# M-Brain.net
KiCad netlist of a schematic drawn in EAGLE
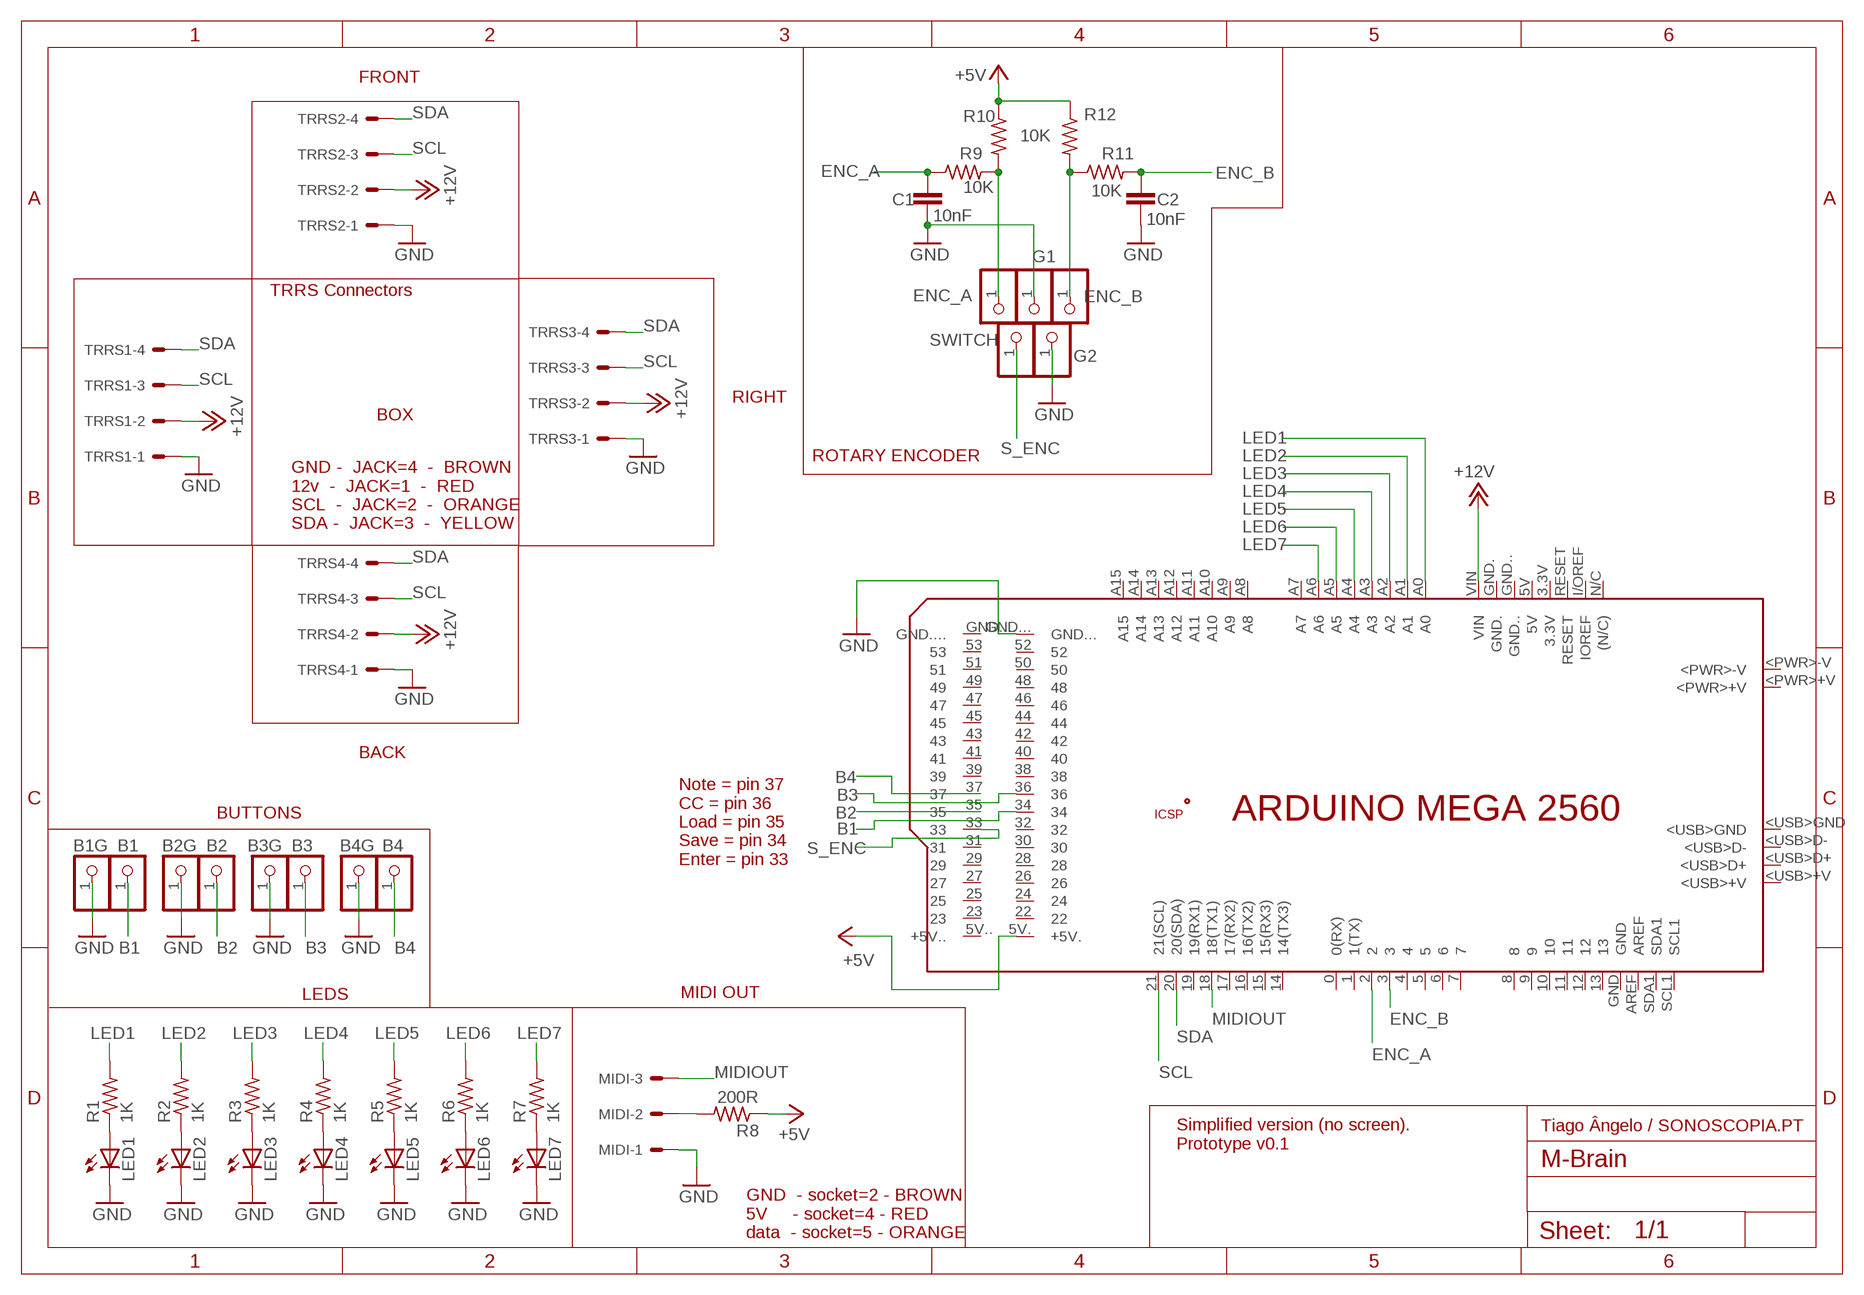
[diagram p0: schematic, sheet 1]

(export (version "E")
  (design (tool "Eeschema 10.0.6"))
  (components
    (comp (ref "B1")
      (value "PINHD-1X1")
      (footprint "eagle-import:1X01")
      (libsource (lib "eagle-import") (part "PINHD-1X1"))
    )
    (comp (ref "B1G")
      (value "PINHD-1X1")
      (footprint "eagle-import:1X01")
      (libsource (lib "eagle-import") (part "PINHD-1X1"))
    )
    (comp (ref "B2")
      (value "PINHD-1X1")
      (footprint "eagle-import:1X01")
      (libsource (lib "eagle-import") (part "PINHD-1X1"))
    )
    (comp (ref "B2G")
      (value "PINHD-1X1")
      (footprint "eagle-import:1X01")
      (libsource (lib "eagle-import") (part "PINHD-1X1"))
    )
    (comp (ref "B3")
      (value "PINHD-1X1")
      (footprint "eagle-import:1X01")
      (libsource (lib "eagle-import") (part "PINHD-1X1"))
    )
    (comp (ref "B3G")
      (value "PINHD-1X1")
      (footprint "eagle-import:1X01")
      (libsource (lib "eagle-import") (part "PINHD-1X1"))
    )
    (comp (ref "B4")
      (value "PINHD-1X1")
      (footprint "eagle-import:1X01")
      (libsource (lib "eagle-import") (part "PINHD-1X1"))
    )
    (comp (ref "B4G")
      (value "PINHD-1X1")
      (footprint "eagle-import:1X01")
      (libsource (lib "eagle-import") (part "PINHD-1X1"))
    )
    (comp (ref "C1")
      (value "10nF")
      (footprint "eagle-import:C2.5-2")
      (libsource (lib "eagle-import") (part "C2.5/2"))
    )
    (comp (ref "C2")
      (value "10nF")
      (footprint "eagle-import:C2.5-2")
      (libsource (lib "eagle-import") (part "C2.5/2"))
    )
    (comp (ref "ENC_A")
      (value "PINHD-1X1")
      (footprint "eagle-import:1X01")
      (libsource (lib "eagle-import") (part "PINHD-1X1"))
    )
    (comp (ref "ENC_B")
      (value "PINHD-1X1")
      (footprint "eagle-import:1X01")
      (libsource (lib "eagle-import") (part "PINHD-1X1"))
    )
    (comp (ref "G1")
      (value "PINHD-1X1")
      (footprint "eagle-import:1X01")
      (libsource (lib "eagle-import") (part "PINHD-1X1"))
    )
    (comp (ref "G2")
      (value "PINHD-1X1")
      (footprint "eagle-import:1X01")
      (libsource (lib "eagle-import") (part "PINHD-1X1"))
    )
    (comp (ref "LED1")
      (value "LED5MM")
      (footprint "eagle-import:LED5MM")
      (libsource (lib "eagle-import") (part "LED5MM"))
    )
    (comp (ref "LED2")
      (value "LED5MM")
      (footprint "eagle-import:LED5MM")
      (libsource (lib "eagle-import") (part "LED5MM"))
    )
    (comp (ref "LED3")
      (value "LED5MM")
      (footprint "eagle-import:LED5MM")
      (libsource (lib "eagle-import") (part "LED5MM"))
    )
    (comp (ref "LED4")
      (value "LED5MM")
      (footprint "eagle-import:LED5MM")
      (libsource (lib "eagle-import") (part "LED5MM"))
    )
    (comp (ref "LED5")
      (value "LED5MM")
      (footprint "eagle-import:LED5MM")
      (libsource (lib "eagle-import") (part "LED5MM"))
    )
    (comp (ref "LED6")
      (value "LED5MM")
      (footprint "eagle-import:LED5MM")
      (libsource (lib "eagle-import") (part "LED5MM"))
    )
    (comp (ref "LED7")
      (value "LED5MM")
      (footprint "eagle-import:LED5MM")
      (libsource (lib "eagle-import") (part "LED5MM"))
    )
    (comp (ref "MIDI")
      (value "22-27-2031-03")
      (footprint "eagle-import:6410-03")
      (libsource (lib "eagle-import") (part "22-?-0327-2031"))
    )
    (comp (ref "PCB1")
      (value "ARDUINO_MEGA2560")
      (footprint "eagle-import:ARDUINO_MEGA2560")
      (libsource (lib "eagle-import") (part "ARDUINO_MEGA2560"))
    )
    (comp (ref "R1")
      (value "1K")
      (footprint "eagle-import:0204_5")
      (libsource (lib "eagle-import") (part "R-US_0204/5"))
    )
    (comp (ref "R2")
      (value "1K")
      (footprint "eagle-import:0204_5")
      (libsource (lib "eagle-import") (part "R-US_0204/5"))
    )
    (comp (ref "R3")
      (value "1K")
      (footprint "eagle-import:0204_5")
      (libsource (lib "eagle-import") (part "R-US_0204/5"))
    )
    (comp (ref "R4")
      (value "1K")
      (footprint "eagle-import:0204_5")
      (libsource (lib "eagle-import") (part "R-US_0204/5"))
    )
    (comp (ref "R5")
      (value "1K")
      (footprint "eagle-import:0204_5")
      (libsource (lib "eagle-import") (part "R-US_0204/5"))
    )
    (comp (ref "R6")
      (value "1K")
      (footprint "eagle-import:0204_5")
      (libsource (lib "eagle-import") (part "R-US_0204/5"))
    )
    (comp (ref "R7")
      (value "1K")
      (footprint "eagle-import:0204_5")
      (libsource (lib "eagle-import") (part "R-US_0204/5"))
    )
    (comp (ref "R8")
      (value "200R")
      (footprint "eagle-import:0204_7")
      (libsource (lib "eagle-import") (part "R-US_0204/7"))
    )
    (comp (ref "R9")
      (value "10K")
      (footprint "eagle-import:0204_7")
      (libsource (lib "eagle-import") (part "R-US_0204/7"))
    )
    (comp (ref "R10")
      (value "10K")
      (footprint "eagle-import:0204_7")
      (libsource (lib "eagle-import") (part "R-US_0204/7"))
    )
    (comp (ref "R11")
      (value "10K")
      (footprint "eagle-import:0204_7")
      (libsource (lib "eagle-import") (part "R-US_0204/7"))
    )
    (comp (ref "R12")
      (value "10K")
      (footprint "eagle-import:0204_7")
      (libsource (lib "eagle-import") (part "R-US_0204/7"))
    )
    (comp (ref "SWITCH")
      (value "PINHD-1X1")
      (footprint "eagle-import:1X01")
      (libsource (lib "eagle-import") (part "PINHD-1X1"))
    )
    (comp (ref "TRRS1")
      (value "22-27-2041-04")
      (footprint "eagle-import:6410-04")
      (libsource (lib "eagle-import") (part "22-?-0427-2041"))
    )
    (comp (ref "TRRS2")
      (value "22-27-2041-04")
      (footprint "eagle-import:6410-04")
      (libsource (lib "eagle-import") (part "22-?-0427-2041"))
    )
    (comp (ref "TRRS3")
      (value "22-27-2041-04")
      (footprint "eagle-import:6410-04")
      (libsource (lib "eagle-import") (part "22-?-0427-2041"))
    )
    (comp (ref "TRRS4")
      (value "22-27-2041-04")
      (footprint "eagle-import:6410-04")
      (libsource (lib "eagle-import") (part "22-?-0427-2041"))
    )
  )
  (nets
    (net (code "1") (name "+5V") (class "Default")
      (node (ref "PCB1") (pin "5V.") (pinfunction "+5V._5V.") (pintype "bidirectional"))
      (node (ref "R10") (pin "1") (pinfunction "1_1") (pintype "passive"))
      (node (ref "R12") (pin "1") (pinfunction "1_1") (pintype "passive"))
      (node (ref "R8") (pin "1") (pinfunction "1_1") (pintype "passive"))
    )
    (net (code "2") (name "+12V") (class "Default")
      (node (ref "PCB1") (pin "VIN") (pinfunction "VIN_VIN") (pintype "bidirectional"))
      (node (ref "TRRS1") (pin "2") (pinfunction "S_2") (pintype "passive"))
      (node (ref "TRRS2") (pin "2") (pinfunction "S_2") (pintype "passive"))
      (node (ref "TRRS3") (pin "2") (pinfunction "S_2") (pintype "passive"))
      (node (ref "TRRS4") (pin "2") (pinfunction "S_2") (pintype "passive"))
    )
    (net (code "3") (name "/B1") (class "Default")
      (node (ref "B1") (pin "1") (pinfunction "1_1") (pintype "passive"))
      (node (ref "PCB1") (pin "34") (pinfunction "34_34") (pintype "bidirectional"))
    )
    (net (code "4") (name "/B2") (class "Default")
      (node (ref "B2") (pin "1") (pinfunction "1_1") (pintype "passive"))
      (node (ref "PCB1") (pin "35") (pinfunction "35_35") (pintype "bidirectional"))
    )
    (net (code "5") (name "/B3") (class "Default")
      (node (ref "B3") (pin "1") (pinfunction "1_1") (pintype "passive"))
      (node (ref "PCB1") (pin "36") (pinfunction "36_36") (pintype "bidirectional"))
    )
    (net (code "6") (name "/B4") (class "Default")
      (node (ref "B4") (pin "1") (pinfunction "1_1") (pintype "passive"))
      (node (ref "PCB1") (pin "37") (pinfunction "37_37") (pintype "bidirectional"))
    )
    (net (code "7") (name "/ENC_A") (class "Default")
      (node (ref "C1") (pin "1") (pinfunction "1_1") (pintype "passive"))
      (node (ref "PCB1") (pin "2") (pinfunction "2_2") (pintype "bidirectional"))
      (node (ref "R9") (pin "1") (pinfunction "1_1") (pintype "passive"))
    )
    (net (code "8") (name "/ENC_B") (class "Default")
      (node (ref "C2") (pin "1") (pinfunction "1_1") (pintype "passive"))
      (node (ref "PCB1") (pin "3") (pinfunction "3_3") (pintype "bidirectional"))
      (node (ref "R11") (pin "2") (pinfunction "2_2") (pintype "passive"))
    )
    (net (code "9") (name "/LED1") (class "Default")
      (node (ref "PCB1") (pin "A0") (pinfunction "A0_A0") (pintype "bidirectional"))
      (node (ref "R1") (pin "2") (pinfunction "2_2") (pintype "passive"))
    )
    (net (code "10") (name "/LED2") (class "Default")
      (node (ref "PCB1") (pin "A1") (pinfunction "A1_A1") (pintype "bidirectional"))
      (node (ref "R2") (pin "2") (pinfunction "2_2") (pintype "passive"))
    )
    (net (code "11") (name "/LED3") (class "Default")
      (node (ref "PCB1") (pin "A2") (pinfunction "A2_A2") (pintype "bidirectional"))
      (node (ref "R3") (pin "2") (pinfunction "2_2") (pintype "passive"))
    )
    (net (code "12") (name "/LED4") (class "Default")
      (node (ref "PCB1") (pin "A3") (pinfunction "A3_A3") (pintype "bidirectional"))
      (node (ref "R4") (pin "2") (pinfunction "2_2") (pintype "passive"))
    )
    (net (code "13") (name "/LED5") (class "Default")
      (node (ref "PCB1") (pin "A4") (pinfunction "A4_A4") (pintype "bidirectional"))
      (node (ref "R5") (pin "2") (pinfunction "2_2") (pintype "passive"))
    )
    (net (code "14") (name "/LED6") (class "Default")
      (node (ref "PCB1") (pin "A5") (pinfunction "A5_A5") (pintype "bidirectional"))
      (node (ref "R6") (pin "2") (pinfunction "2_2") (pintype "passive"))
    )
    (net (code "15") (name "/LED7") (class "Default")
      (node (ref "PCB1") (pin "A6") (pinfunction "A6_A6") (pintype "bidirectional"))
      (node (ref "R7") (pin "2") (pinfunction "2_2") (pintype "passive"))
    )
    (net (code "16") (name "/MIDIOUT") (class "Default")
      (node (ref "MIDI") (pin "3") (pinfunction "S_3") (pintype "passive"))
      (node (ref "PCB1") (pin "18") (pinfunction "18(TX1)_18") (pintype "bidirectional"))
    )
    (net (code "17") (name "/SCL") (class "Default")
      (node (ref "PCB1") (pin "21") (pinfunction "21(SCL)_21") (pintype "bidirectional"))
      (node (ref "TRRS1") (pin "3") (pinfunction "S_3") (pintype "passive"))
      (node (ref "TRRS2") (pin "3") (pinfunction "S_3") (pintype "passive"))
      (node (ref "TRRS3") (pin "3") (pinfunction "S_3") (pintype "passive"))
      (node (ref "TRRS4") (pin "3") (pinfunction "S_3") (pintype "passive"))
    )
    (net (code "18") (name "/SDA") (class "Default")
      (node (ref "PCB1") (pin "20") (pinfunction "20(SDA)_20") (pintype "bidirectional"))
      (node (ref "TRRS1") (pin "4") (pinfunction "S_4") (pintype "passive"))
      (node (ref "TRRS2") (pin "4") (pinfunction "S_4") (pintype "passive"))
      (node (ref "TRRS3") (pin "4") (pinfunction "S_4") (pintype "passive"))
      (node (ref "TRRS4") (pin "4") (pinfunction "S_4") (pintype "passive"))
    )
    (net (code "19") (name "/S_ENC") (class "Default")
      (node (ref "PCB1") (pin "33") (pinfunction "33_33") (pintype "bidirectional"))
      (node (ref "SWITCH") (pin "1") (pinfunction "1_1") (pintype "passive"))
    )
    (net (code "20") (name "GND") (class "Default")
      (node (ref "B1G") (pin "1") (pinfunction "1_1") (pintype "passive"))
      (node (ref "B2G") (pin "1") (pinfunction "1_1") (pintype "passive"))
      (node (ref "B3G") (pin "1") (pinfunction "1_1") (pintype "passive"))
      (node (ref "B4G") (pin "1") (pinfunction "1_1") (pintype "passive"))
      (node (ref "C1") (pin "2") (pinfunction "2_2") (pintype "passive"))
      (node (ref "C2") (pin "2") (pinfunction "2_2") (pintype "passive"))
      (node (ref "G1") (pin "1") (pinfunction "1_1") (pintype "passive"))
      (node (ref "G2") (pin "1") (pinfunction "1_1") (pintype "passive"))
      (node (ref "LED1") (pin "K") (pinfunction "C_K") (pintype "passive"))
      (node (ref "LED2") (pin "K") (pinfunction "C_K") (pintype "passive"))
      (node (ref "LED3") (pin "K") (pinfunction "C_K") (pintype "passive"))
      (node (ref "LED4") (pin "K") (pinfunction "C_K") (pintype "passive"))
      (node (ref "LED5") (pin "K") (pinfunction "C_K") (pintype "passive"))
      (node (ref "LED6") (pin "K") (pinfunction "C_K") (pintype "passive"))
      (node (ref "LED7") (pin "K") (pinfunction "C_K") (pintype "passive"))
      (node (ref "MIDI") (pin "1") (pinfunction "S_1") (pintype "passive"))
      (node (ref "PCB1") (pin "GND...") (pinfunction "GND..._GND...") (pintype "bidirectional"))
      (node (ref "TRRS1") (pin "1") (pinfunction "S_1") (pintype "passive"))
      (node (ref "TRRS2") (pin "1") (pinfunction "S_1") (pintype "passive"))
      (node (ref "TRRS3") (pin "1") (pinfunction "S_1") (pintype "passive"))
      (node (ref "TRRS4") (pin "1") (pinfunction "S_1") (pintype "passive"))
    )
    (net (code "21") (name "Net-(ENC_A-Pad1)") (class "Default")
      (node (ref "ENC_A") (pin "1") (pinfunction "1_1") (pintype "passive"))
      (node (ref "R10") (pin "2") (pinfunction "2_2") (pintype "passive"))
      (node (ref "R9") (pin "2") (pinfunction "2_2") (pintype "passive"))
    )
    (net (code "22") (name "Net-(ENC_B-Pad1)") (class "Default")
      (node (ref "ENC_B") (pin "1") (pinfunction "1_1") (pintype "passive"))
      (node (ref "R11") (pin "1") (pinfunction "1_1") (pintype "passive"))
      (node (ref "R12") (pin "2") (pinfunction "2_2") (pintype "passive"))
    )
    (net (code "23") (name "Net-(LED1-PadA)") (class "Default")
      (node (ref "LED1") (pin "A") (pinfunction "A_A") (pintype "passive"))
      (node (ref "R1") (pin "1") (pinfunction "1_1") (pintype "passive"))
    )
    (net (code "24") (name "Net-(LED2-PadA)") (class "Default")
      (node (ref "LED2") (pin "A") (pinfunction "A_A") (pintype "passive"))
      (node (ref "R2") (pin "1") (pinfunction "1_1") (pintype "passive"))
    )
    (net (code "25") (name "Net-(LED3-PadA)") (class "Default")
      (node (ref "LED3") (pin "A") (pinfunction "A_A") (pintype "passive"))
      (node (ref "R3") (pin "1") (pinfunction "1_1") (pintype "passive"))
    )
    (net (code "26") (name "Net-(LED4-PadA)") (class "Default")
      (node (ref "LED4") (pin "A") (pinfunction "A_A") (pintype "passive"))
      (node (ref "R4") (pin "1") (pinfunction "1_1") (pintype "passive"))
    )
    (net (code "27") (name "Net-(LED5-PadA)") (class "Default")
      (node (ref "LED5") (pin "A") (pinfunction "A_A") (pintype "passive"))
      (node (ref "R5") (pin "1") (pinfunction "1_1") (pintype "passive"))
    )
    (net (code "28") (name "Net-(LED6-PadA)") (class "Default")
      (node (ref "LED6") (pin "A") (pinfunction "A_A") (pintype "passive"))
      (node (ref "R6") (pin "1") (pinfunction "1_1") (pintype "passive"))
    )
    (net (code "29") (name "Net-(LED7-PadA)") (class "Default")
      (node (ref "LED7") (pin "A") (pinfunction "A_A") (pintype "passive"))
      (node (ref "R7") (pin "1") (pinfunction "1_1") (pintype "passive"))
    )
    (net (code "30") (name "Net-(MIDIB-S)") (class "Default")
      (node (ref "MIDI") (pin "2") (pinfunction "S_2") (pintype "passive"))
      (node (ref "R8") (pin "2") (pinfunction "2_2") (pintype "passive"))
    )
    (net (code "31") (name "unconnected-(PCB1-(N{slash}C)-PadN{slash}C)") (class "Default")
      (node (ref "PCB1") (pin "N/C") (pinfunction "(N/C)_N/C") (pintype "bidirectional"))
    )
    (net (code "32") (name "unconnected-(PCB1-+5V..-Pad5V..)") (class "Default")
      (node (ref "PCB1") (pin "5V..") (pinfunction "+5V.._5V..") (pintype "bidirectional"))
    )
    (net (code "33") (name "unconnected-(PCB1-0(RX)-Pad0)") (class "Default")
      (node (ref "PCB1") (pin "0") (pinfunction "0(RX)_0") (pintype "bidirectional"))
    )
    (net (code "34") (name "unconnected-(PCB1-1(TX)-Pad1)") (class "Default")
      (node (ref "PCB1") (pin "1") (pinfunction "1(TX)_1") (pintype "bidirectional"))
    )
    (net (code "35") (name "unconnected-(PCB1-14(TX3)-Pad14)") (class "Default")
      (node (ref "PCB1") (pin "14") (pinfunction "14(TX3)_14") (pintype "bidirectional"))
    )
    (net (code "36") (name "unconnected-(PCB1-15(RX3)-Pad15)") (class "Default")
      (node (ref "PCB1") (pin "15") (pinfunction "15(RX3)_15") (pintype "bidirectional"))
    )
    (net (code "37") (name "unconnected-(PCB1-16(TX2)-Pad16)") (class "Default")
      (node (ref "PCB1") (pin "16") (pinfunction "16(TX2)_16") (pintype "bidirectional"))
    )
    (net (code "38") (name "unconnected-(PCB1-17(RX2)-Pad17)") (class "Default")
      (node (ref "PCB1") (pin "17") (pinfunction "17(RX2)_17") (pintype "bidirectional"))
    )
    (net (code "39") (name "unconnected-(PCB1-19(RX1)-Pad19)") (class "Default")
      (node (ref "PCB1") (pin "19") (pinfunction "19(RX1)_19") (pintype "bidirectional"))
    )
    (net (code "40") (name "unconnected-(PCB1-IOREF-PadI{slash}OREF)") (class "Default")
      (node (ref "PCB1") (pin "I/OREF") (pinfunction "IOREF_I/OREF") (pintype "bidirectional"))
    )
    (net (code "41") (name "unconnected-(PCB1-Pad+5V_)") (class "Default")
      (node (ref "PCB1") (pin "+5V_") (pinfunction "+5V__+5V_") (pintype "bidirectional"))
    )
    (net (code "42") (name "unconnected-(PCB1-Pad3.3V)") (class "Default")
      (node (ref "PCB1") (pin "3.3V") (pinfunction "3.3V_3.3V") (pintype "bidirectional"))
    )
    (net (code "43") (name "unconnected-(PCB1-Pad4)") (class "Default")
      (node (ref "PCB1") (pin "4") (pinfunction "4_4") (pintype "bidirectional"))
    )
    (net (code "44") (name "unconnected-(PCB1-Pad5)") (class "Default")
      (node (ref "PCB1") (pin "5") (pinfunction "5_5") (pintype "bidirectional"))
    )
    (net (code "45") (name "unconnected-(PCB1-Pad5V)") (class "Default")
      (node (ref "PCB1") (pin "5V") (pinfunction "5V_5V") (pintype "bidirectional"))
    )
    (net (code "46") (name "unconnected-(PCB1-Pad6)") (class "Default")
      (node (ref "PCB1") (pin "6") (pinfunction "6_6") (pintype "bidirectional"))
    )
    (net (code "47") (name "unconnected-(PCB1-Pad7)") (class "Default")
      (node (ref "PCB1") (pin "7") (pinfunction "7_7") (pintype "bidirectional"))
    )
    (net (code "48") (name "unconnected-(PCB1-Pad8)") (class "Default")
      (node (ref "PCB1") (pin "8") (pinfunction "8_8") (pintype "bidirectional"))
    )
    (net (code "49") (name "unconnected-(PCB1-Pad9)") (class "Default")
      (node (ref "PCB1") (pin "9") (pinfunction "9_9") (pintype "bidirectional"))
    )
    (net (code "50") (name "unconnected-(PCB1-Pad10)") (class "Default")
      (node (ref "PCB1") (pin "10") (pinfunction "10_10") (pintype "bidirectional"))
    )
    (net (code "51") (name "unconnected-(PCB1-Pad11)") (class "Default")
      (node (ref "PCB1") (pin "11") (pinfunction "11_11") (pintype "bidirectional"))
    )
    (net (code "52") (name "unconnected-(PCB1-Pad12)") (class "Default")
      (node (ref "PCB1") (pin "12") (pinfunction "12_12") (pintype "bidirectional"))
    )
    (net (code "53") (name "unconnected-(PCB1-Pad13)") (class "Default")
      (node (ref "PCB1") (pin "13") (pinfunction "13_13") (pintype "bidirectional"))
    )
    (net (code "54") (name "unconnected-(PCB1-Pad22)") (class "Default")
      (node (ref "PCB1") (pin "22") (pinfunction "22_22") (pintype "bidirectional"))
    )
    (net (code "55") (name "unconnected-(PCB1-Pad23)") (class "Default")
      (node (ref "PCB1") (pin "23") (pinfunction "23_23") (pintype "bidirectional"))
    )
    (net (code "56") (name "unconnected-(PCB1-Pad24)") (class "Default")
      (node (ref "PCB1") (pin "24") (pinfunction "24_24") (pintype "bidirectional"))
    )
    (net (code "57") (name "unconnected-(PCB1-Pad25)") (class "Default")
      (node (ref "PCB1") (pin "25") (pinfunction "25_25") (pintype "bidirectional"))
    )
    (net (code "58") (name "unconnected-(PCB1-Pad26)") (class "Default")
      (node (ref "PCB1") (pin "26") (pinfunction "26_26") (pintype "bidirectional"))
    )
    (net (code "59") (name "unconnected-(PCB1-Pad27)") (class "Default")
      (node (ref "PCB1") (pin "27") (pinfunction "27_27") (pintype "bidirectional"))
    )
    (net (code "60") (name "unconnected-(PCB1-Pad28)") (class "Default")
      (node (ref "PCB1") (pin "28") (pinfunction "28_28") (pintype "bidirectional"))
    )
    (net (code "61") (name "unconnected-(PCB1-Pad29)") (class "Default")
      (node (ref "PCB1") (pin "29") (pinfunction "29_29") (pintype "bidirectional"))
    )
    (net (code "62") (name "unconnected-(PCB1-Pad30)") (class "Default")
      (node (ref "PCB1") (pin "30") (pinfunction "30_30") (pintype "bidirectional"))
    )
    (net (code "63") (name "unconnected-(PCB1-Pad31)") (class "Default")
      (node (ref "PCB1") (pin "31") (pinfunction "31_31") (pintype "bidirectional"))
    )
    (net (code "64") (name "unconnected-(PCB1-Pad32)") (class "Default")
      (node (ref "PCB1") (pin "32") (pinfunction "32_32") (pintype "bidirectional"))
    )
    (net (code "65") (name "unconnected-(PCB1-Pad38)") (class "Default")
      (node (ref "PCB1") (pin "38") (pinfunction "38_38") (pintype "bidirectional"))
    )
    (net (code "66") (name "unconnected-(PCB1-Pad39)") (class "Default")
      (node (ref "PCB1") (pin "39") (pinfunction "39_39") (pintype "bidirectional"))
    )
    (net (code "67") (name "unconnected-(PCB1-Pad40)") (class "Default")
      (node (ref "PCB1") (pin "40") (pinfunction "40_40") (pintype "bidirectional"))
    )
    (net (code "68") (name "unconnected-(PCB1-Pad41)") (class "Default")
      (node (ref "PCB1") (pin "41") (pinfunction "41_41") (pintype "bidirectional"))
    )
    (net (code "69") (name "unconnected-(PCB1-Pad42)") (class "Default")
      (node (ref "PCB1") (pin "42") (pinfunction "42_42") (pintype "bidirectional"))
    )
    (net (code "70") (name "unconnected-(PCB1-Pad43)") (class "Default")
      (node (ref "PCB1") (pin "43") (pinfunction "43_43") (pintype "bidirectional"))
    )
    (net (code "71") (name "unconnected-(PCB1-Pad44)") (class "Default")
      (node (ref "PCB1") (pin "44") (pinfunction "44_44") (pintype "bidirectional"))
    )
    (net (code "72") (name "unconnected-(PCB1-Pad45)") (class "Default")
      (node (ref "PCB1") (pin "45") (pinfunction "45_45") (pintype "bidirectional"))
    )
    (net (code "73") (name "unconnected-(PCB1-Pad46)") (class "Default")
      (node (ref "PCB1") (pin "46") (pinfunction "46_46") (pintype "bidirectional"))
    )
    (net (code "74") (name "unconnected-(PCB1-Pad47)") (class "Default")
      (node (ref "PCB1") (pin "47") (pinfunction "47_47") (pintype "bidirectional"))
    )
    (net (code "75") (name "unconnected-(PCB1-Pad48)") (class "Default")
      (node (ref "PCB1") (pin "48") (pinfunction "48_48") (pintype "bidirectional"))
    )
    (net (code "76") (name "unconnected-(PCB1-Pad49)") (class "Default")
      (node (ref "PCB1") (pin "49") (pinfunction "49_49") (pintype "bidirectional"))
    )
    (net (code "77") (name "unconnected-(PCB1-Pad50)") (class "Default")
      (node (ref "PCB1") (pin "50") (pinfunction "50_50") (pintype "bidirectional"))
    )
    (net (code "78") (name "unconnected-(PCB1-Pad51)") (class "Default")
      (node (ref "PCB1") (pin "51") (pinfunction "51_51") (pintype "bidirectional"))
    )
    (net (code "79") (name "unconnected-(PCB1-Pad52)") (class "Default")
      (node (ref "PCB1") (pin "52") (pinfunction "52_52") (pintype "bidirectional"))
    )
    (net (code "80") (name "unconnected-(PCB1-Pad53)") (class "Default")
      (node (ref "PCB1") (pin "53") (pinfunction "53_53") (pintype "bidirectional"))
    )
    (net (code "81") (name "unconnected-(PCB1-Pad<PWR>+V)") (class "Default")
      (node (ref "PCB1") (pin "<PWR>+V") (pinfunction "<PWR>+V_<PWR>+V") (pintype "no_connect"))
    )
    (net (code "82") (name "unconnected-(PCB1-Pad<PWR>-V)") (class "Default")
      (node (ref "PCB1") (pin "<PWR>-V") (pinfunction "<PWR>-V_<PWR>-V") (pintype "no_connect"))
    )
    (net (code "83") (name "unconnected-(PCB1-Pad<USB>+V)") (class "Default")
      (node (ref "PCB1") (pin "<USB>+V") (pinfunction "<USB>+V_<USB>+V") (pintype "no_connect"))
    )
    (net (code "84") (name "unconnected-(PCB1-Pad<USB>D+)") (class "Default")
      (node (ref "PCB1") (pin "<USB>D+") (pinfunction "<USB>D+_<USB>D+") (pintype "no_connect"))
    )
    (net (code "85") (name "unconnected-(PCB1-Pad<USB>D-)") (class "Default")
      (node (ref "PCB1") (pin "<USB>D-") (pinfunction "<USB>D-_<USB>D-") (pintype "no_connect"))
    )
    (net (code "86") (name "unconnected-(PCB1-Pad<USB>GND)") (class "Default")
      (node (ref "PCB1") (pin "<USB>GND") (pinfunction "<USB>GND_<USB>GND") (pintype "no_connect"))
    )
    (net (code "87") (name "unconnected-(PCB1-PadA7)") (class "Default")
      (node (ref "PCB1") (pin "A7") (pinfunction "A7_A7") (pintype "bidirectional"))
    )
    (net (code "88") (name "unconnected-(PCB1-PadA8)") (class "Default")
      (node (ref "PCB1") (pin "A8") (pinfunction "A8_A8") (pintype "bidirectional"))
    )
    (net (code "89") (name "unconnected-(PCB1-PadA9)") (class "Default")
      (node (ref "PCB1") (pin "A9") (pinfunction "A9_A9") (pintype "bidirectional"))
    )
    (net (code "90") (name "unconnected-(PCB1-PadA10)") (class "Default")
      (node (ref "PCB1") (pin "A10") (pinfunction "A10_A10") (pintype "bidirectional"))
    )
    (net (code "91") (name "unconnected-(PCB1-PadA11)") (class "Default")
      (node (ref "PCB1") (pin "A11") (pinfunction "A11_A11") (pintype "bidirectional"))
    )
    (net (code "92") (name "unconnected-(PCB1-PadA12)") (class "Default")
      (node (ref "PCB1") (pin "A12") (pinfunction "A12_A12") (pintype "bidirectional"))
    )
    (net (code "93") (name "unconnected-(PCB1-PadA13)") (class "Default")
      (node (ref "PCB1") (pin "A13") (pinfunction "A13_A13") (pintype "bidirectional"))
    )
    (net (code "94") (name "unconnected-(PCB1-PadA14)") (class "Default")
      (node (ref "PCB1") (pin "A14") (pinfunction "A14_A14") (pintype "bidirectional"))
    )
    (net (code "95") (name "unconnected-(PCB1-PadA15)") (class "Default")
      (node (ref "PCB1") (pin "A15") (pinfunction "A15_A15") (pintype "bidirectional"))
    )
    (net (code "96") (name "unconnected-(PCB1-PadAREF)") (class "Default")
      (node (ref "PCB1") (pin "AREF") (pinfunction "AREF_AREF") (pintype "bidirectional"))
    )
    (net (code "97") (name "unconnected-(PCB1-PadGND)") (class "Default")
      (node (ref "PCB1") (pin "GND") (pinfunction "GND_GND") (pintype "bidirectional"))
    )
    (net (code "98") (name "unconnected-(PCB1-PadGND.)") (class "Default")
      (node (ref "PCB1") (pin "GND.") (pinfunction "GND._GND.") (pintype "bidirectional"))
    )
    (net (code "99") (name "unconnected-(PCB1-PadGND..)") (class "Default")
      (node (ref "PCB1") (pin "GND..") (pinfunction "GND.._GND..") (pintype "bidirectional"))
    )
    (net (code "100") (name "unconnected-(PCB1-PadGND....)") (class "Default")
      (node (ref "PCB1") (pin "GND....") (pinfunction "GND...._GND....") (pintype "bidirectional"))
    )
    (net (code "101") (name "unconnected-(PCB1-PadGND__)") (class "Default")
      (node (ref "PCB1") (pin "GND__") (pinfunction "GND___GND__") (pintype "bidirectional"))
    )
    (net (code "102") (name "unconnected-(PCB1-PadMISO)") (class "Default")
      (node (ref "PCB1") (pin "MISO") (pinfunction "MISO_MISO") (pintype "bidirectional"))
    )
    (net (code "103") (name "unconnected-(PCB1-PadMOSI)") (class "Default")
      (node (ref "PCB1") (pin "MOSI") (pinfunction "MOSI_MOSI") (pintype "bidirectional"))
    )
    (net (code "104") (name "unconnected-(PCB1-PadRESET)") (class "Default")
      (node (ref "PCB1") (pin "RESET") (pinfunction "RESET_RESET") (pintype "bidirectional"))
    )
    (net (code "105") (name "unconnected-(PCB1-PadRESET.)") (class "Default")
      (node (ref "PCB1") (pin "RESET.") (pinfunction "RESET._RESET.") (pintype "bidirectional"))
    )
    (net (code "106") (name "unconnected-(PCB1-PadSCK)") (class "Default")
      (node (ref "PCB1") (pin "SCK") (pinfunction "SCK_SCK") (pintype "bidirectional"))
    )
    (net (code "107") (name "unconnected-(PCB1-PadSCL1)") (class "Default")
      (node (ref "PCB1") (pin "SCL1") (pinfunction "SCL1_SCL1") (pintype "bidirectional"))
    )
    (net (code "108") (name "unconnected-(PCB1-PadSDA1)") (class "Default")
      (node (ref "PCB1") (pin "SDA1") (pinfunction "SDA1_SDA1") (pintype "bidirectional"))
    )
  )
)
